# SmartTeaMachinePCB.net
KiCad netlist of a schematic drawn in EAGLE
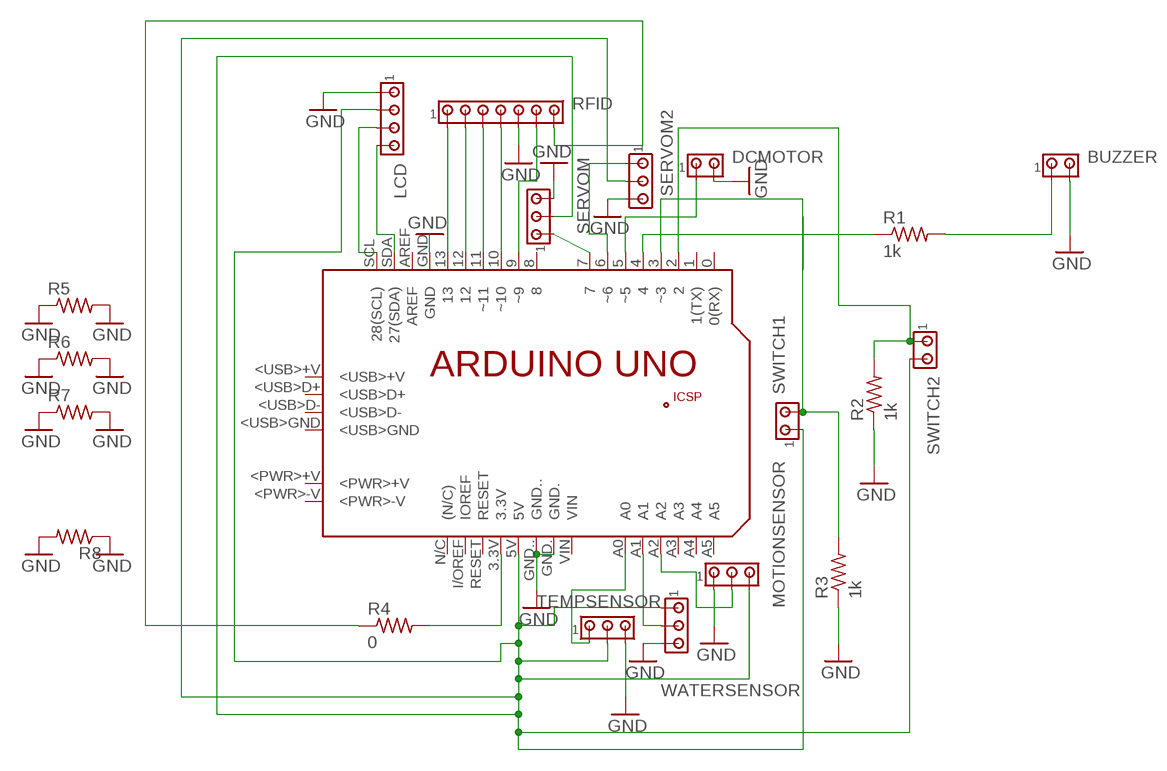
[diagram p0: schematic, sheet 1]

(export (version "E")
  (design (tool "Eeschema 10.0.6"))
  (components
    (comp (ref "BUZZER")
      (value "MTA02-100")
      (footprint "eagle-import:10X02MTA")
      (libsource (lib "eagle-import") (part "MTA02-100"))
    )
    (comp (ref "DCMOTOR")
      (value "MTA02-100")
      (footprint "eagle-import:10X02MTA")
      (libsource (lib "eagle-import") (part "MTA02-100"))
    )
    (comp (ref "LCD")
      (value "MTA04-100")
      (footprint "eagle-import:10X04MTA")
      (libsource (lib "eagle-import") (part "MTA04-100"))
    )
    (comp (ref "MOTIONSENSOR")
      (value "MTA03-100")
      (footprint "eagle-import:10X03MTA")
      (libsource (lib "eagle-import") (part "MTA03-100"))
    )
    (comp (ref "PCB1")
      (value "ARDUINO_UNO")
      (footprint "eagle-import:ARDUINO_UNO")
      (libsource (lib "eagle-import") (part "ARDUINO_UNO"))
    )
    (comp (ref "R1")
      (value "1k")
      (footprint "eagle-import:0207_10")
      (libsource (lib "eagle-import") (part "R-US_0207/10"))
    )
    (comp (ref "R2")
      (value "1k")
      (footprint "eagle-import:0207_10")
      (libsource (lib "eagle-import") (part "R-US_0207/10"))
    )
    (comp (ref "R3")
      (value "1k")
      (footprint "eagle-import:0207_10")
      (libsource (lib "eagle-import") (part "R-US_0207/10"))
    )
    (comp (ref "R4")
      (value "0")
      (footprint "eagle-import:0207_10")
      (libsource (lib "eagle-import") (part "R-US_0207/10"))
    )
    (comp (ref "R5")
      (value "R-US_0207/10")
      (footprint "eagle-import:0207_10")
      (libsource (lib "eagle-import") (part "R-US_0207/10"))
    )
    (comp (ref "R6")
      (value "R-US_0207/10")
      (footprint "eagle-import:0207_10")
      (libsource (lib "eagle-import") (part "R-US_0207/10"))
    )
    (comp (ref "R7")
      (value "R-US_0207/10")
      (footprint "eagle-import:0207_10")
      (libsource (lib "eagle-import") (part "R-US_0207/10"))
    )
    (comp (ref "R8")
      (value "R-US_0207/10")
      (footprint "eagle-import:0207_10")
      (libsource (lib "eagle-import") (part "R-US_0207/10"))
    )
    (comp (ref "RFID")
      (value "MTA07-100")
      (footprint "eagle-import:10X07MTA")
      (libsource (lib "eagle-import") (part "MTA07-100"))
    )
    (comp (ref "SERVOM")
      (value "MTA03-100")
      (footprint "eagle-import:10X03MTA")
      (libsource (lib "eagle-import") (part "MTA03-100"))
    )
    (comp (ref "SERVOM2")
      (value "MTA03-100")
      (footprint "eagle-import:10X03MTA")
      (libsource (lib "eagle-import") (part "MTA03-100"))
    )
    (comp (ref "SWITCH1")
      (value "MTA02-100")
      (footprint "eagle-import:10X02MTA")
      (libsource (lib "eagle-import") (part "MTA02-100"))
    )
    (comp (ref "SWITCH2")
      (value "MTA02-100")
      (footprint "eagle-import:10X02MTA")
      (libsource (lib "eagle-import") (part "MTA02-100"))
    )
    (comp (ref "TEMPSENSOR")
      (value "MTA03-100")
      (footprint "eagle-import:10X03MTA")
      (libsource (lib "eagle-import") (part "MTA03-100"))
    )
    (comp (ref "WATERSENSOR")
      (value "MTA03-100")
      (footprint "eagle-import:10X03MTA")
      (libsource (lib "eagle-import") (part "MTA03-100"))
    )
  )
  (nets
    (net (code "1") (name "GND") (class "Default")
      (node (ref "BUZZER") (pin "2") (pinfunction "2_2") (pintype "passive"))
      (node (ref "DCMOTOR") (pin "2") (pinfunction "2_2") (pintype "passive"))
      (node (ref "LCD") (pin "1") (pinfunction "1_1") (pintype "passive"))
      (node (ref "MOTIONSENSOR") (pin "1") (pinfunction "1_1") (pintype "passive"))
      (node (ref "PCB1") (pin "GND") (pinfunction "GND_GND") (pintype "bidirectional"))
      (node (ref "PCB1") (pin "GND.") (pinfunction "GND._GND.") (pintype "bidirectional"))
      (node (ref "PCB1") (pin "GND..") (pinfunction "GND.._GND..") (pintype "bidirectional"))
      (node (ref "R2") (pin "1") (pinfunction "1_1") (pintype "passive"))
      (node (ref "R3") (pin "1") (pinfunction "1_1") (pintype "passive"))
      (node (ref "R5") (pin "1") (pinfunction "1_1") (pintype "passive"))
      (node (ref "R5") (pin "2") (pinfunction "2_2") (pintype "passive"))
      (node (ref "R6") (pin "1") (pinfunction "1_1") (pintype "passive"))
      (node (ref "R6") (pin "2") (pinfunction "2_2") (pintype "passive"))
      (node (ref "R7") (pin "1") (pinfunction "1_1") (pintype "passive"))
      (node (ref "R7") (pin "2") (pinfunction "2_2") (pintype "passive"))
      (node (ref "R8") (pin "1") (pinfunction "1_1") (pintype "passive"))
      (node (ref "R8") (pin "2") (pinfunction "2_2") (pintype "passive"))
      (node (ref "RFID") (pin "5") (pinfunction "5_5") (pintype "passive"))
      (node (ref "SERVOM") (pin "3") (pinfunction "3_3") (pintype "passive"))
      (node (ref "SERVOM2") (pin "3") (pinfunction "3_3") (pintype "passive"))
      (node (ref "TEMPSENSOR") (pin "3") (pinfunction "3_3") (pintype "passive"))
      (node (ref "WATERSENSOR") (pin "3") (pinfunction "3_3") (pintype "passive"))
    )
    (net (code "2") (name "Net-(BUZZER-Pad1)") (class "Default")
      (node (ref "BUZZER") (pin "1") (pinfunction "1_1") (pintype "passive"))
      (node (ref "R1") (pin "2") (pinfunction "2_2") (pintype "passive"))
    )
    (net (code "3") (name "Net-(LCD-Pad2)") (class "Default")
      (node (ref "LCD") (pin "2") (pinfunction "2_2") (pintype "passive"))
      (node (ref "MOTIONSENSOR") (pin "3") (pinfunction "3_3") (pintype "passive"))
      (node (ref "PCB1") (pin "5V") (pinfunction "5V_5V") (pintype "bidirectional"))
      (node (ref "SERVOM") (pin "2") (pinfunction "2_2") (pintype "passive"))
      (node (ref "SERVOM2") (pin "2") (pinfunction "2_2") (pintype "passive"))
      (node (ref "SWITCH1") (pin "1") (pinfunction "1_1") (pintype "passive"))
      (node (ref "SWITCH2") (pin "2") (pinfunction "2_2") (pintype "passive"))
      (node (ref "TEMPSENSOR") (pin "2") (pinfunction "2_2") (pintype "passive"))
      (node (ref "WATERSENSOR") (pin "1") (pinfunction "1_1") (pintype "passive"))
    )
    (net (code "4") (name "Net-(MOTIONSENSOR-Pad2)") (class "Default")
      (node (ref "MOTIONSENSOR") (pin "2") (pinfunction "2_2") (pintype "passive"))
      (node (ref "PCB1") (pin "A2") (pinfunction "A2_A2") (pintype "bidirectional"))
    )
    (net (code "5") (name "Net-(PCB1-27(SDA))") (class "Default")
      (node (ref "LCD") (pin "4") (pinfunction "4_4") (pintype "passive"))
      (node (ref "PCB1") (pin "SDA") (pinfunction "27(SDA)_SDA") (pintype "bidirectional"))
    )
    (net (code "6") (name "Net-(PCB1-28(SCL))") (class "Default")
      (node (ref "LCD") (pin "3") (pinfunction "3_3") (pintype "passive"))
      (node (ref "PCB1") (pin "SCL") (pinfunction "28(SCL)_SCL") (pintype "bidirectional"))
    )
    (net (code "7") (name "Net-(PCB1-Pad2)") (class "Default")
      (node (ref "PCB1") (pin "2") (pinfunction "2_2") (pintype "bidirectional"))
      (node (ref "R2") (pin "2") (pinfunction "2_2") (pintype "passive"))
      (node (ref "SWITCH2") (pin "1") (pinfunction "1_1") (pintype "passive"))
    )
    (net (code "8") (name "Net-(PCB1-Pad3.3V)") (class "Default")
      (node (ref "PCB1") (pin "3.3V") (pinfunction "3.3V_3.3V") (pintype "bidirectional"))
      (node (ref "R4") (pin "2") (pinfunction "2_2") (pintype "passive"))
    )
    (net (code "9") (name "Net-(PCB1-Pad4)") (class "Default")
      (node (ref "PCB1") (pin "4") (pinfunction "4_4") (pintype "bidirectional"))
      (node (ref "R1") (pin "1") (pinfunction "1_1") (pintype "passive"))
    )
    (net (code "10") (name "Net-(PCB1-Pad7)") (class "Default")
      (node (ref "PCB1") (pin "7") (pinfunction "7_7") (pintype "bidirectional"))
      (node (ref "SERVOM") (pin "1") (pinfunction "1_1") (pintype "passive"))
    )
    (net (code "11") (name "Net-(PCB1-Pad12)") (class "Default")
      (node (ref "PCB1") (pin "12") (pinfunction "12_12") (pintype "bidirectional"))
      (node (ref "RFID") (pin "2") (pinfunction "2_2") (pintype "passive"))
    )
    (net (code "12") (name "Net-(PCB1-Pad13)") (class "Default")
      (node (ref "PCB1") (pin "13") (pinfunction "13_13") (pintype "bidirectional"))
      (node (ref "RFID") (pin "1") (pinfunction "1_1") (pintype "passive"))
    )
    (net (code "13") (name "Net-(PCB1-PadA0)") (class "Default")
      (node (ref "PCB1") (pin "A0") (pinfunction "A0_A0") (pintype "bidirectional"))
      (node (ref "TEMPSENSOR") (pin "1") (pinfunction "1_1") (pintype "passive"))
    )
    (net (code "14") (name "Net-(PCB1-PadA1)") (class "Default")
      (node (ref "PCB1") (pin "A1") (pinfunction "A1_A1") (pintype "bidirectional"))
      (node (ref "WATERSENSOR") (pin "2") (pinfunction "2_2") (pintype "passive"))
    )
    (net (code "15") (name "Net-(PCB1-~{3})") (class "Default")
      (node (ref "PCB1") (pin "3") (pinfunction "~{3}_3") (pintype "bidirectional"))
      (node (ref "R3") (pin "2") (pinfunction "2_2") (pintype "passive"))
      (node (ref "SWITCH1") (pin "2") (pinfunction "2_2") (pintype "passive"))
    )
    (net (code "16") (name "Net-(PCB1-~{5})") (class "Default")
      (node (ref "DCMOTOR") (pin "1") (pinfunction "1_1") (pintype "passive"))
      (node (ref "PCB1") (pin "5") (pinfunction "~{5}_5") (pintype "bidirectional"))
    )
    (net (code "17") (name "Net-(PCB1-~{6})") (class "Default")
      (node (ref "PCB1") (pin "6") (pinfunction "~{6}_6") (pintype "bidirectional"))
      (node (ref "SERVOM2") (pin "1") (pinfunction "1_1") (pintype "passive"))
    )
    (net (code "18") (name "Net-(PCB1-~{9})") (class "Default")
      (node (ref "PCB1") (pin "9") (pinfunction "~{9}_9") (pintype "bidirectional"))
      (node (ref "RFID") (pin "6") (pinfunction "6_6") (pintype "passive"))
    )
    (net (code "19") (name "Net-(PCB1-~{10})") (class "Default")
      (node (ref "PCB1") (pin "10") (pinfunction "~{10}_10") (pintype "bidirectional"))
      (node (ref "RFID") (pin "4") (pinfunction "4_4") (pintype "passive"))
    )
    (net (code "20") (name "Net-(PCB1-~{11})") (class "Default")
      (node (ref "PCB1") (pin "11") (pinfunction "~{11}_11") (pintype "bidirectional"))
      (node (ref "RFID") (pin "3") (pinfunction "3_3") (pintype "passive"))
    )
    (net (code "21") (name "Net-(R4-Pad1)") (class "Default")
      (node (ref "R4") (pin "1") (pinfunction "1_1") (pintype "passive"))
      (node (ref "RFID") (pin "7") (pinfunction "7_7") (pintype "passive"))
    )
    (net (code "22") (name "unconnected-(PCB1-(N{slash}C)-PadN{slash}C)") (class "Default")
      (node (ref "PCB1") (pin "N/C") (pinfunction "(N/C)_N/C") (pintype "bidirectional"))
    )
    (net (code "23") (name "unconnected-(PCB1-0(RX)-Pad0)") (class "Default")
      (node (ref "PCB1") (pin "0") (pinfunction "0(RX)_0") (pintype "bidirectional"))
    )
    (net (code "24") (name "unconnected-(PCB1-1(TX)-Pad1)") (class "Default")
      (node (ref "PCB1") (pin "1") (pinfunction "1(TX)_1") (pintype "bidirectional"))
    )
    (net (code "25") (name "unconnected-(PCB1-IOREF-PadI{slash}OREF)") (class "Default")
      (node (ref "PCB1") (pin "I/OREF") (pinfunction "IOREF_I/OREF") (pintype "bidirectional"))
    )
    (net (code "26") (name "unconnected-(PCB1-Pad+5V)") (class "Default")
      (node (ref "PCB1") (pin "+5V") (pinfunction "+5V_+5V") (pintype "bidirectional"))
    )
    (net (code "27") (name "unconnected-(PCB1-Pad8)") (class "Default")
      (node (ref "PCB1") (pin "8") (pinfunction "8_8") (pintype "bidirectional"))
    )
    (net (code "28") (name "unconnected-(PCB1-Pad<PWR>+V)") (class "Default")
      (node (ref "PCB1") (pin "<PWR>+V") (pinfunction "<PWR>+V_<PWR>+V") (pintype "bidirectional"))
    )
    (net (code "29") (name "unconnected-(PCB1-Pad<PWR>-V)") (class "Default")
      (node (ref "PCB1") (pin "<PWR>-V") (pinfunction "<PWR>-V_<PWR>-V") (pintype "bidirectional"))
    )
    (net (code "30") (name "unconnected-(PCB1-Pad<USB>+V)") (class "Default")
      (node (ref "PCB1") (pin "<USB>+V") (pinfunction "<USB>+V_<USB>+V") (pintype "bidirectional"))
    )
    (net (code "31") (name "unconnected-(PCB1-Pad<USB>D+)") (class "Default")
      (node (ref "PCB1") (pin "<USB>D+") (pinfunction "<USB>D+_<USB>D+") (pintype "bidirectional"))
    )
    (net (code "32") (name "unconnected-(PCB1-Pad<USB>D-)") (class "Default")
      (node (ref "PCB1") (pin "<USB>D-") (pinfunction "<USB>D-_<USB>D-") (pintype "bidirectional"))
    )
    (net (code "33") (name "unconnected-(PCB1-Pad<USB>GND)") (class "Default")
      (node (ref "PCB1") (pin "<USB>GND") (pinfunction "<USB>GND_<USB>GND") (pintype "bidirectional"))
    )
    (net (code "34") (name "unconnected-(PCB1-PadA3)") (class "Default")
      (node (ref "PCB1") (pin "A3") (pinfunction "A3_A3") (pintype "bidirectional"))
    )
    (net (code "35") (name "unconnected-(PCB1-PadA4)") (class "Default")
      (node (ref "PCB1") (pin "A4") (pinfunction "A4_A4") (pintype "bidirectional"))
    )
    (net (code "36") (name "unconnected-(PCB1-PadA5)") (class "Default")
      (node (ref "PCB1") (pin "A5") (pinfunction "A5_A5") (pintype "bidirectional"))
    )
    (net (code "37") (name "unconnected-(PCB1-PadAREF)") (class "Default")
      (node (ref "PCB1") (pin "AREF") (pinfunction "AREF_AREF") (pintype "bidirectional"))
    )
    (net (code "38") (name "unconnected-(PCB1-PadGND_)") (class "Default")
      (node (ref "PCB1") (pin "GND_") (pinfunction "GND__GND_") (pintype "bidirectional"))
    )
    (net (code "39") (name "unconnected-(PCB1-PadMISO)") (class "Default")
      (node (ref "PCB1") (pin "MISO") (pinfunction "MISO_MISO") (pintype "bidirectional"))
    )
    (net (code "40") (name "unconnected-(PCB1-PadMOSI)") (class "Default")
      (node (ref "PCB1") (pin "MOSI") (pinfunction "MOSI_MOSI") (pintype "bidirectional"))
    )
    (net (code "41") (name "unconnected-(PCB1-PadRESET)") (class "Default")
      (node (ref "PCB1") (pin "RESET") (pinfunction "RESET_RESET") (pintype "bidirectional"))
    )
    (net (code "42") (name "unconnected-(PCB1-PadRESET.)") (class "Default")
      (node (ref "PCB1") (pin "RESET.") (pinfunction "RESET._RESET.") (pintype "bidirectional"))
    )
    (net (code "43") (name "unconnected-(PCB1-PadSCK)") (class "Default")
      (node (ref "PCB1") (pin "SCK") (pinfunction "SCK_SCK") (pintype "bidirectional"))
    )
    (net (code "44") (name "unconnected-(PCB1-PadVIN)") (class "Default")
      (node (ref "PCB1") (pin "VIN") (pinfunction "VIN_VIN") (pintype "bidirectional"))
    )
  )
)
